# unitygain.net
KiCad netlist of a schematic drawn in EAGLE
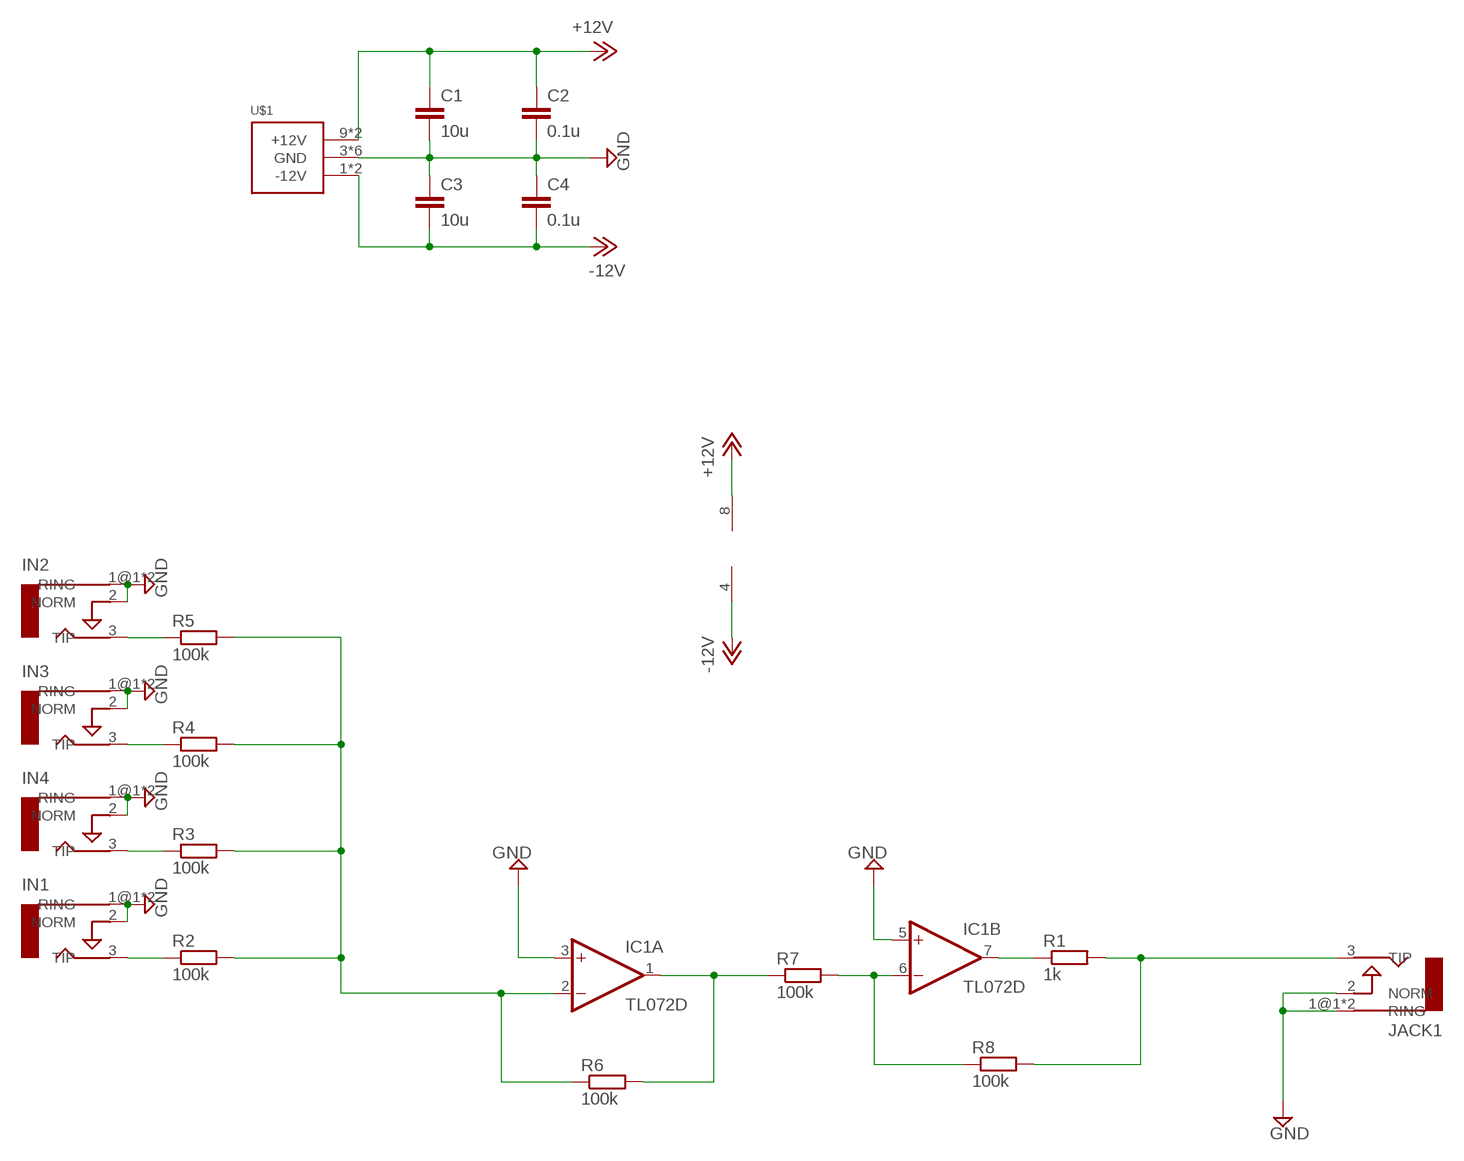
[diagram p0: schematic, sheet 1]

(export (version "E")
  (design (tool "Eeschema 10.0.6"))
  (components
    (comp (ref "C1")
      (value "10u")
      (footprint "eagle-import:C0805")
      (libsource (lib "eagle-import") (part "C-EUC0805"))
    )
    (comp (ref "C2")
      (value "0.1u")
      (footprint "eagle-import:C0805")
      (libsource (lib "eagle-import") (part "C-EUC0805"))
    )
    (comp (ref "C3")
      (value "10u")
      (footprint "eagle-import:C0805")
      (libsource (lib "eagle-import") (part "C-EUC0805"))
    )
    (comp (ref "C4")
      (value "0.1u")
      (footprint "eagle-import:C0805")
      (libsource (lib "eagle-import") (part "C-EUC0805"))
    )
    (comp (ref "IC1")
      (value "TL072D")
      (footprint "eagle-import:SO08")
      (libsource (lib "eagle-import") (part "TL072D"))
    )
    (comp (ref "IN1")
      (value "IN1")
      (footprint "eagle-import:ERTHENVAR-JACK")
      (libsource (lib "eagle-import") (part "AUDIO-JACKERTHENVAR"))
    )
    (comp (ref "IN2")
      (value "IN2")
      (footprint "eagle-import:ERTHENVAR-JACK")
      (libsource (lib "eagle-import") (part "AUDIO-JACKERTHENVAR"))
    )
    (comp (ref "IN3")
      (value "IN3")
      (footprint "eagle-import:ERTHENVAR-JACK")
      (libsource (lib "eagle-import") (part "AUDIO-JACKERTHENVAR"))
    )
    (comp (ref "IN4")
      (value "IN4")
      (footprint "eagle-import:ERTHENVAR-JACK")
      (libsource (lib "eagle-import") (part "AUDIO-JACKERTHENVAR"))
    )
    (comp (ref "JACK1")
      (value "OUT")
      (footprint "eagle-import:ERTHENVAR-JACK")
      (libsource (lib "eagle-import") (part "AUDIO-JACKERTHENVAR"))
    )
    (comp (ref "R1")
      (value "1k")
      (footprint "eagle-import:R0805")
      (libsource (lib "eagle-import") (part "R-EU_R0805"))
    )
    (comp (ref "R2")
      (value "100k")
      (footprint "eagle-import:R0805")
      (libsource (lib "eagle-import") (part "R-EU_R0805"))
    )
    (comp (ref "R3")
      (value "100k")
      (footprint "eagle-import:R0805")
      (libsource (lib "eagle-import") (part "R-EU_R0805"))
    )
    (comp (ref "R4")
      (value "100k")
      (footprint "eagle-import:R0805")
      (libsource (lib "eagle-import") (part "R-EU_R0805"))
    )
    (comp (ref "R5")
      (value "100k")
      (footprint "eagle-import:R0805")
      (libsource (lib "eagle-import") (part "R-EU_R0805"))
    )
    (comp (ref "R6")
      (value "100k")
      (footprint "eagle-import:R0805")
      (libsource (lib "eagle-import") (part "R-EU_R0805"))
    )
    (comp (ref "R7")
      (value "100k")
      (footprint "eagle-import:R0805")
      (libsource (lib "eagle-import") (part "R-EU_R0805"))
    )
    (comp (ref "R8")
      (value "100k")
      (footprint "eagle-import:R0805")
      (libsource (lib "eagle-import") (part "R-EU_R0805"))
    )
    (comp (ref "U$1")
      (value "POWER_SIMPLE10")
      (footprint "eagle-import:POWER_10")
      (libsource (lib "eagle-import") (part "POWER_SIMPLE10"))
    )
  )
  (nets
    (net (code "1") (name "+12V") (class "Default")
      (node (ref "C1") (pin "1") (pinfunction "1_1") (pintype "passive"))
      (node (ref "C2") (pin "1") (pinfunction "1_1") (pintype "passive"))
      (node (ref "IC1") (pin "8") (pinfunction "V+_8") (pintype "power_in"))
      (node (ref "U$1") (pin "10") (pinfunction "+12V_10") (pintype "bidirectional"))
      (node (ref "U$1") (pin "9") (pinfunction "+12V_9") (pintype "bidirectional"))
    )
    (net (code "2") (name "-12V") (class "Default")
      (node (ref "C3") (pin "2") (pinfunction "2_2") (pintype "passive"))
      (node (ref "C4") (pin "2") (pinfunction "2_2") (pintype "passive"))
      (node (ref "IC1") (pin "4") (pinfunction "V-_4") (pintype "power_in"))
      (node (ref "U$1") (pin "1") (pinfunction "-12V_1") (pintype "bidirectional"))
      (node (ref "U$1") (pin "2") (pinfunction "-12V_2") (pintype "bidirectional"))
    )
    (net (code "3") (name "GND") (class "Default")
      (node (ref "C1") (pin "2") (pinfunction "2_2") (pintype "passive"))
      (node (ref "C2") (pin "2") (pinfunction "2_2") (pintype "passive"))
      (node (ref "C3") (pin "1") (pinfunction "1_1") (pintype "passive"))
      (node (ref "C4") (pin "1") (pinfunction "1_1") (pintype "passive"))
      (node (ref "IC1") (pin "3") (pinfunction "+IN_3") (pintype "input"))
      (node (ref "IC1") (pin "5") (pinfunction "+IN_5") (pintype "input"))
      (node (ref "IN1") (pin "1@1") (pinfunction "RING_1@1") (pintype "bidirectional"))
      (node (ref "IN1") (pin "1@2") (pinfunction "RING_1@2") (pintype "bidirectional"))
      (node (ref "IN1") (pin "2") (pinfunction "NORM_2") (pintype "bidirectional"))
      (node (ref "IN2") (pin "1@1") (pinfunction "RING_1@1") (pintype "bidirectional"))
      (node (ref "IN2") (pin "1@2") (pinfunction "RING_1@2") (pintype "bidirectional"))
      (node (ref "IN2") (pin "2") (pinfunction "NORM_2") (pintype "bidirectional"))
      (node (ref "IN3") (pin "1@1") (pinfunction "RING_1@1") (pintype "bidirectional"))
      (node (ref "IN3") (pin "1@2") (pinfunction "RING_1@2") (pintype "bidirectional"))
      (node (ref "IN3") (pin "2") (pinfunction "NORM_2") (pintype "bidirectional"))
      (node (ref "IN4") (pin "1@1") (pinfunction "RING_1@1") (pintype "bidirectional"))
      (node (ref "IN4") (pin "1@2") (pinfunction "RING_1@2") (pintype "bidirectional"))
      (node (ref "IN4") (pin "2") (pinfunction "NORM_2") (pintype "bidirectional"))
      (node (ref "JACK1") (pin "1@1") (pinfunction "RING_1@1") (pintype "bidirectional"))
      (node (ref "JACK1") (pin "1@2") (pinfunction "RING_1@2") (pintype "bidirectional"))
      (node (ref "JACK1") (pin "2") (pinfunction "NORM_2") (pintype "bidirectional"))
      (node (ref "U$1") (pin "3") (pinfunction "GND_3") (pintype "bidirectional"))
      (node (ref "U$1") (pin "4") (pinfunction "GND_4") (pintype "bidirectional"))
      (node (ref "U$1") (pin "5") (pinfunction "GND_5") (pintype "bidirectional"))
      (node (ref "U$1") (pin "6") (pinfunction "GND_6") (pintype "bidirectional"))
      (node (ref "U$1") (pin "7") (pinfunction "GND_7") (pintype "bidirectional"))
      (node (ref "U$1") (pin "8") (pinfunction "GND_8") (pintype "bidirectional"))
    )
    (net (code "4") (name "Net-(IC1A--IN)") (class "Default")
      (node (ref "IC1") (pin "2") (pinfunction "-IN_2") (pintype "input"))
      (node (ref "R2") (pin "2") (pinfunction "2_2") (pintype "passive"))
      (node (ref "R3") (pin "2") (pinfunction "2_2") (pintype "passive"))
      (node (ref "R4") (pin "2") (pinfunction "2_2") (pintype "passive"))
      (node (ref "R5") (pin "2") (pinfunction "2_2") (pintype "passive"))
      (node (ref "R6") (pin "1") (pinfunction "1_1") (pintype "passive"))
    )
    (net (code "5") (name "Net-(IC1A-OUT)") (class "Default")
      (node (ref "IC1") (pin "1") (pinfunction "OUT_1") (pintype "output"))
      (node (ref "R6") (pin "2") (pinfunction "2_2") (pintype "passive"))
      (node (ref "R7") (pin "1") (pinfunction "1_1") (pintype "passive"))
    )
    (net (code "6") (name "Net-(IC1B--IN)") (class "Default")
      (node (ref "IC1") (pin "6") (pinfunction "-IN_6") (pintype "input"))
      (node (ref "R7") (pin "2") (pinfunction "2_2") (pintype "passive"))
      (node (ref "R8") (pin "1") (pinfunction "1_1") (pintype "passive"))
    )
    (net (code "7") (name "Net-(IC1B-OUT)") (class "Default")
      (node (ref "IC1") (pin "7") (pinfunction "OUT_7") (pintype "output"))
      (node (ref "R1") (pin "1") (pinfunction "1_1") (pintype "passive"))
    )
    (net (code "8") (name "Net-(IN1-TIP)") (class "Default")
      (node (ref "IN1") (pin "3") (pinfunction "TIP_3") (pintype "bidirectional"))
      (node (ref "R2") (pin "1") (pinfunction "1_1") (pintype "passive"))
    )
    (net (code "9") (name "Net-(IN2-TIP)") (class "Default")
      (node (ref "IN2") (pin "3") (pinfunction "TIP_3") (pintype "bidirectional"))
      (node (ref "R5") (pin "1") (pinfunction "1_1") (pintype "passive"))
    )
    (net (code "10") (name "Net-(IN3-TIP)") (class "Default")
      (node (ref "IN3") (pin "3") (pinfunction "TIP_3") (pintype "bidirectional"))
      (node (ref "R4") (pin "1") (pinfunction "1_1") (pintype "passive"))
    )
    (net (code "11") (name "Net-(IN4-TIP)") (class "Default")
      (node (ref "IN4") (pin "3") (pinfunction "TIP_3") (pintype "bidirectional"))
      (node (ref "R3") (pin "1") (pinfunction "1_1") (pintype "passive"))
    )
    (net (code "12") (name "Net-(JACK1-TIP)") (class "Default")
      (node (ref "JACK1") (pin "3") (pinfunction "TIP_3") (pintype "bidirectional"))
      (node (ref "R1") (pin "2") (pinfunction "2_2") (pintype "passive"))
      (node (ref "R8") (pin "2") (pinfunction "2_2") (pintype "passive"))
    )
  )
)
